# DC_Motor.net
KiCad netlist of a schematic drawn in Altium Designer
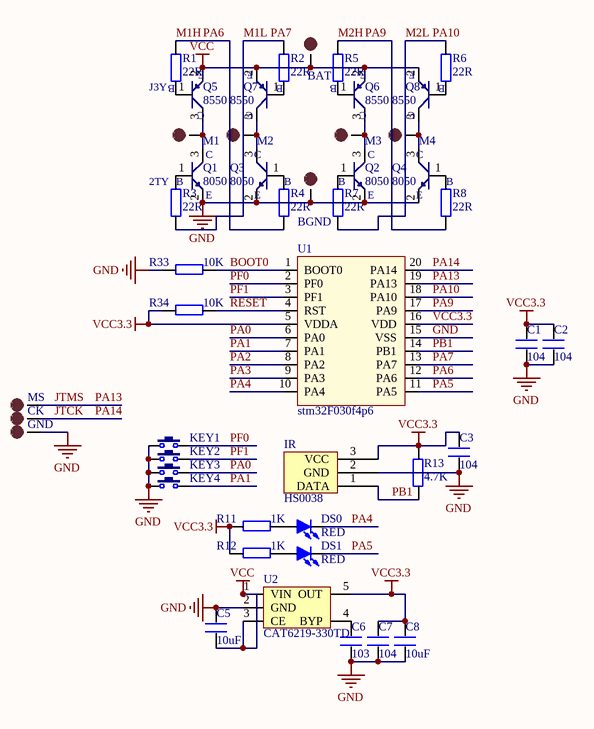
[diagram p0: DC_Motor.SchDoc]

(export (version "E")
  (design (tool "Eeschema 10.0.6"))
  (components
    (comp (ref "BAT")
      (value "TEST")
      (footprint "TP-1.5")
      (description "测试点")
      (libsource (lib "号令者I.MX RT底板封装库") (part "TEST-POINT"))
    )
    (comp (ref "BGND")
      (value "TEST")
      (footprint "TP-1.5")
      (description "测试点")
      (libsource (lib "号令者I.MX RT底板封装库") (part "TEST-POINT"))
    )
    (comp (ref "C1") (value "104") (footprint "C 0603_L") (libsource (lib "号令者I.MX RT底板封装库") (part "C")))
    (comp (ref "C2") (value "104") (footprint "C 0603_L") (libsource (lib "号令者I.MX RT底板封装库") (part "C")))
    (comp (ref "C3") (value "104") (footprint "C 0603_L") (libsource (lib "号令者I.MX RT底板封装库") (part "C")))
    (comp (ref "C5")
      (value "10uF")
      (footprint "C 0603_L")
      (libsource (lib "WarShip V3 STM32103封装库") (part "C"))
    )
    (comp (ref "C6")
      (value "103")
      (footprint "C 0603_L")
      (libsource (lib "WarShip V3 STM32103封装库") (part "C"))
    )
    (comp (ref "C7")
      (value "104")
      (footprint "C 0603_L")
      (libsource (lib "WarShip V3 STM32103封装库") (part "C"))
    )
    (comp (ref "C8")
      (value "10uF")
      (footprint "C 0603_L")
      (libsource (lib "WarShip V3 STM32103封装库") (part "C"))
    )
    (comp (ref "CK")
      (value "TEST POINT")
      (footprint "TP-1.5")
      (description "测试点")
      (libsource (lib "STM32F767核心板封装库") (part "TEST-POINT"))
    )
    (comp (ref "DS0")
      (value "RED")
      (footprint "LED 0805R")
      (description "贴片LED")
      (fields (field (name "版权归属") "源创客"))
      (libsource (lib "LED") (part "LED-SMD"))
    )
    (comp (ref "DS1")
      (value "RED")
      (footprint "LED 0805R")
      (description "贴片LED")
      (fields (field (name "版权归属") "源创客"))
      (libsource (lib "LED") (part "LED-SMD"))
    )
    (comp (ref "GND")
      (value "TEST POINT")
      (footprint "TP-1.5")
      (description "测试点")
      (libsource (lib "STM32F767核心板封装库") (part "TEST-POINT"))
    )
    (comp (ref "IR")
      (value "HS0038")
      (footprint "29-04")
      (libsource (lib "阿波罗STM32F4&F7底板封装库") (part "HS0038"))
    )
    (comp (ref "KEY1")
      (value "KEY")
      (footprint "TSW DIP-6*6*5 - 2")
      (description "按键")
      (fields (field (name "版权归属") "源创客"))
      (libsource (lib "IMX6UL_ALPHA(底板)_V2.0") (part "KEY"))
    )
    (comp (ref "KEY2")
      (value "KEY")
      (footprint "TSW DIP-6*6*5 - 2")
      (description "按键")
      (fields (field (name "版权归属") "源创客"))
      (libsource (lib "IMX6UL_ALPHA(底板)_V2.0") (part "KEY"))
    )
    (comp (ref "KEY3")
      (value "KEY")
      (footprint "TSW DIP-6*6*5 - 2")
      (description "按键")
      (fields (field (name "版权归属") "源创客"))
      (libsource (lib "IMX6UL_ALPHA(底板)_V2.0") (part "KEY"))
    )
    (comp (ref "KEY4")
      (value "KEY")
      (footprint "TSW DIP-6*6*5 - 2")
      (description "按键")
      (fields (field (name "版权归属") "源创客"))
      (libsource (lib "IMX6UL_ALPHA(底板)_V2.0") (part "KEY"))
    )
    (comp (ref "M1")
      (value "TEST")
      (footprint "TP-1.5")
      (description "测试点")
      (libsource (lib "号令者I.MX RT底板封装库") (part "TEST-POINT"))
    )
    (comp (ref "M2")
      (value "TEST")
      (footprint "TP-1.5")
      (description "测试点")
      (libsource (lib "号令者I.MX RT底板封装库") (part "TEST-POINT"))
    )
    (comp (ref "M3")
      (value "TEST")
      (footprint "TP-1.5")
      (description "测试点")
      (libsource (lib "号令者I.MX RT底板封装库") (part "TEST-POINT"))
    )
    (comp (ref "M4")
      (value "TEST")
      (footprint "TP-1.5")
      (description "测试点")
      (libsource (lib "号令者I.MX RT底板封装库") (part "TEST-POINT"))
    )
    (comp (ref "MS")
      (value "TEST POINT")
      (footprint "TP-1.5")
      (description "测试点")
      (libsource (lib "STM32F767核心板封装库") (part "TEST-POINT"))
    )
    (comp (ref "Q1") (value "8050") (footprint "SOT23-3L") (libsource (lib "ESP32_Weather") (part "8050NPN")))
    (comp (ref "Q2") (value "8050") (footprint "SOT23-3L") (libsource (lib "ESP32_Weather") (part "8050NPN")))
    (comp (ref "Q3") (value "8050") (footprint "SOT23-3L") (libsource (lib "ESP32_Weather") (part "8050NPN")))
    (comp (ref "Q4") (value "8050") (footprint "SOT23-3L") (libsource (lib "ESP32_Weather") (part "8050NPN")))
    (comp (ref "Q5") (value "8550") (footprint "SOT23-3L") (libsource (lib "ESP32_Weather") (part "8550PNP")))
    (comp (ref "Q6") (value "8550") (footprint "SOT23-3L") (libsource (lib "ESP32_Weather") (part "8550PNP")))
    (comp (ref "Q7") (value "8550") (footprint "SOT23-3L") (libsource (lib "ESP32_Weather") (part "8550PNP")))
    (comp (ref "Q8") (value "8550") (footprint "SOT23-3L") (libsource (lib "ESP32_Weather") (part "8550PNP")))
    (comp (ref "R1") (value "22R") (footprint "R 0603_L") (libsource (lib "号令者I.MX RT底板封装库") (part "R")))
    (comp (ref "R2") (value "22R") (footprint "R 0603_L") (libsource (lib "号令者I.MX RT底板封装库") (part "R")))
    (comp (ref "R3") (value "22R") (footprint "R 0603_L") (libsource (lib "号令者I.MX RT底板封装库") (part "R")))
    (comp (ref "R4") (value "22R") (footprint "R 0603_L") (libsource (lib "号令者I.MX RT底板封装库") (part "R")))
    (comp (ref "R5") (value "22R") (footprint "R 0603_L") (libsource (lib "号令者I.MX RT底板封装库") (part "R")))
    (comp (ref "R6") (value "22R") (footprint "R 0603_L") (libsource (lib "号令者I.MX RT底板封装库") (part "R")))
    (comp (ref "R7") (value "22R") (footprint "R 0603_L") (libsource (lib "号令者I.MX RT底板封装库") (part "R")))
    (comp (ref "R8") (value "22R") (footprint "R 0603_L") (libsource (lib "号令者I.MX RT底板封装库") (part "R")))
    (comp (ref "R11")
      (value "1K")
      (footprint "R 0603_L")
      (libsource (lib "WarShip V3 STM32103封装库") (part "R"))
    )
    (comp (ref "R12")
      (value "1K")
      (footprint "R 0603_L")
      (libsource (lib "WarShip V3 STM32103封装库") (part "R"))
    )
    (comp (ref "R13")
      (value "4.7K")
      (footprint "R 0603_L")
      (libsource (lib "WarShip V3 STM32103封装库") (part "R"))
    )
    (comp (ref "R33")
      (value "10K")
      (footprint "R 0603_L")
      (libsource (lib "WarShip V3 STM32103封装库") (part "R"))
    )
    (comp (ref "R34")
      (value "10K")
      (footprint "R 0603_L")
      (libsource (lib "WarShip V3 STM32103封装库") (part "R"))
    )
    (comp (ref "U1")
      (value "stm32F030f4p6")
      (footprint "TSSOP20_N")
      (libsource (lib "oled_model") (part "stm32f030"))
    )
    (comp (ref "U2")
      (value "CAT6219-330TD")
      (footprint "SOT23-5L")
      (description "3.3V 500mA LDO")
      (libsource (lib "STM32H743核心板封装库") (part "CAT6219-330TD"))
    )
  )
  (nets
    (net (code "1") (name "/BOOT0") (class "Default")
      (node (ref "R33") (pin "1") (pintype "passive"))
      (node (ref "U1") (pin "1") (pinfunction "BOOT0_1") (pintype "passive"))
    )
    (net (code "2") (name "/JTCK") (class "Default")
      (node (ref "CK") (pin "1") (pinfunction "1_1") (pintype "passive"))
      (node (ref "U1") (pin "20") (pinfunction "PA14_20") (pintype "passive"))
    )
    (net (code "3") (name "/JTMS") (class "Default")
      (node (ref "MS") (pin "1") (pinfunction "1_1") (pintype "passive"))
      (node (ref "U1") (pin "19") (pinfunction "PA13_19") (pintype "passive"))
    )
    (net (code "4") (name "/M1H") (class "Default")
      (node (ref "R1") (pin "2") (pintype "passive"))
      (node (ref "R4") (pin "1") (pintype "passive"))
      (node (ref "U1") (pin "12") (pinfunction "PA6_12") (pintype "passive"))
    )
    (net (code "5") (name "/M1L") (class "Default")
      (node (ref "R2") (pin "2") (pintype "passive"))
      (node (ref "R3") (pin "1") (pintype "passive"))
      (node (ref "U1") (pin "13") (pinfunction "PA7_13") (pintype "passive"))
    )
    (net (code "6") (name "/M2H") (class "Default")
      (node (ref "R5") (pin "2") (pintype "passive"))
      (node (ref "R8") (pin "1") (pintype "passive"))
      (node (ref "U1") (pin "17") (pinfunction "PA9_17") (pintype "passive"))
    )
    (net (code "7") (name "/M2L") (class "Default")
      (node (ref "R6") (pin "2") (pintype "passive"))
      (node (ref "R7") (pin "1") (pintype "passive"))
      (node (ref "U1") (pin "18") (pinfunction "PA10_18") (pintype "passive"))
    )
    (net (code "8") (name "/PA0") (class "Default")
      (node (ref "KEY3") (pin "2") (pinfunction "2_2") (pintype "passive"))
      (node (ref "U1") (pin "6") (pinfunction "PA0_6") (pintype "passive"))
    )
    (net (code "9") (name "/PA1") (class "Default")
      (node (ref "KEY4") (pin "2") (pinfunction "2_2") (pintype "passive"))
      (node (ref "U1") (pin "7") (pinfunction "PA1_7") (pintype "passive"))
    )
    (net (code "10") (name "/PA2") (class "Default")
      (node (ref "U1") (pin "8") (pinfunction "PA2_8") (pintype "passive"))
    )
    (net (code "11") (name "/PA3") (class "Default")
      (node (ref "U1") (pin "9") (pinfunction "PA3_9") (pintype "passive"))
    )
    (net (code "12") (name "/PA4") (class "Default")
      (node (ref "DS0") (pin "2") (pinfunction "K_2") (pintype "passive"))
      (node (ref "U1") (pin "10") (pinfunction "PA4_10") (pintype "passive"))
    )
    (net (code "13") (name "/PA5") (class "Default")
      (node (ref "DS1") (pin "2") (pinfunction "K_2") (pintype "passive"))
      (node (ref "U1") (pin "11") (pinfunction "PA5_11") (pintype "passive"))
    )
    (net (code "14") (name "/PB1") (class "Default")
      (node (ref "IR") (pin "1") (pinfunction "DATA_1") (pintype "passive"))
      (node (ref "R13") (pin "2") (pintype "passive"))
      (node (ref "U1") (pin "14") (pinfunction "PB1_14") (pintype "passive"))
    )
    (net (code "15") (name "/PF0") (class "Default")
      (node (ref "KEY1") (pin "2") (pinfunction "2_2") (pintype "passive"))
      (node (ref "U1") (pin "2") (pinfunction "PF0_2") (pintype "passive"))
    )
    (net (code "16") (name "/PF1") (class "Default")
      (node (ref "KEY2") (pin "2") (pinfunction "2_2") (pintype "passive"))
      (node (ref "U1") (pin "3") (pinfunction "PF1_3") (pintype "passive"))
    )
    (net (code "17") (name "/RESET") (class "Default")
      (node (ref "R34") (pin "1") (pintype "passive"))
      (node (ref "U1") (pin "4") (pinfunction "RST_4") (pintype "passive"))
    )
    (net (code "18") (name "GND") (class "Default")
      (node (ref "BGND") (pin "1") (pinfunction "1_1") (pintype "passive"))
      (node (ref "C1") (pin "1") (pintype "passive"))
      (node (ref "C2") (pin "1") (pintype "passive"))
      (node (ref "C3") (pin "1") (pintype "passive"))
      (node (ref "C5") (pin "2") (pintype "passive"))
      (node (ref "C6") (pin "1") (pintype "passive"))
      (node (ref "C7") (pin "1") (pintype "passive"))
      (node (ref "C8") (pin "1") (pintype "passive"))
      (node (ref "GND") (pin "1") (pinfunction "1_1") (pintype "passive"))
      (node (ref "IR") (pin "2") (pinfunction "GND_2") (pintype "passive"))
      (node (ref "KEY1") (pin "1") (pinfunction "1_1") (pintype "passive"))
      (node (ref "KEY2") (pin "1") (pinfunction "1_1") (pintype "passive"))
      (node (ref "KEY3") (pin "1") (pinfunction "1_1") (pintype "passive"))
      (node (ref "KEY4") (pin "1") (pinfunction "1_1") (pintype "passive"))
      (node (ref "Q1") (pin "2") (pinfunction "E_2") (pintype "passive"))
      (node (ref "Q2") (pin "2") (pinfunction "E_2") (pintype "passive"))
      (node (ref "Q3") (pin "2") (pinfunction "E_2") (pintype "passive"))
      (node (ref "Q4") (pin "2") (pinfunction "E_2") (pintype "passive"))
      (node (ref "R33") (pin "2") (pintype "passive"))
      (node (ref "U1") (pin "15") (pinfunction "VSS_15") (pintype "passive"))
      (node (ref "U2") (pin "2") (pinfunction "GND_2") (pintype "passive"))
    )
    (net (code "19") (name "Net-(DS0-A)") (class "Default")
      (node (ref "DS0") (pin "1") (pinfunction "A_1") (pintype "passive"))
      (node (ref "R11") (pin "1") (pintype "passive"))
    )
    (net (code "20") (name "Net-(DS1-A)") (class "Default")
      (node (ref "DS1") (pin "1") (pinfunction "A_1") (pintype "passive"))
      (node (ref "R12") (pin "1") (pintype "passive"))
    )
    (net (code "21") (name "Net-(Q1-B)") (class "Default")
      (node (ref "Q1") (pin "1") (pinfunction "B_1") (pintype "passive"))
      (node (ref "R3") (pin "2") (pintype "passive"))
    )
    (net (code "22") (name "Net-(Q1-C)") (class "Default")
      (node (ref "M1") (pin "1") (pinfunction "1_1") (pintype "passive"))
      (node (ref "Q1") (pin "3") (pinfunction "C_3") (pintype "passive"))
      (node (ref "Q5") (pin "3") (pinfunction "C_3") (pintype "passive"))
    )
    (net (code "23") (name "Net-(Q2-B)") (class "Default")
      (node (ref "Q2") (pin "1") (pinfunction "B_1") (pintype "passive"))
      (node (ref "R7") (pin "2") (pintype "passive"))
    )
    (net (code "24") (name "Net-(Q2-C)") (class "Default")
      (node (ref "M3") (pin "1") (pinfunction "1_1") (pintype "passive"))
      (node (ref "Q2") (pin "3") (pinfunction "C_3") (pintype "passive"))
      (node (ref "Q6") (pin "3") (pinfunction "C_3") (pintype "passive"))
    )
    (net (code "25") (name "Net-(Q3-B)") (class "Default")
      (node (ref "Q3") (pin "1") (pinfunction "B_1") (pintype "passive"))
      (node (ref "R4") (pin "2") (pintype "passive"))
    )
    (net (code "26") (name "Net-(Q3-C)") (class "Default")
      (node (ref "M2") (pin "1") (pinfunction "1_1") (pintype "passive"))
      (node (ref "Q3") (pin "3") (pinfunction "C_3") (pintype "passive"))
      (node (ref "Q7") (pin "3") (pinfunction "C_3") (pintype "passive"))
    )
    (net (code "27") (name "Net-(Q4-B)") (class "Default")
      (node (ref "Q4") (pin "1") (pinfunction "B_1") (pintype "passive"))
      (node (ref "R8") (pin "2") (pintype "passive"))
    )
    (net (code "28") (name "Net-(Q4-C)") (class "Default")
      (node (ref "M4") (pin "1") (pinfunction "1_1") (pintype "passive"))
      (node (ref "Q4") (pin "3") (pinfunction "C_3") (pintype "passive"))
      (node (ref "Q8") (pin "3") (pinfunction "C_3") (pintype "passive"))
    )
    (net (code "29") (name "Net-(Q5-B)") (class "Default")
      (node (ref "Q5") (pin "1") (pinfunction "B_1") (pintype "passive"))
      (node (ref "R1") (pin "1") (pintype "passive"))
    )
    (net (code "30") (name "Net-(Q6-B)") (class "Default")
      (node (ref "Q6") (pin "1") (pinfunction "B_1") (pintype "passive"))
      (node (ref "R5") (pin "1") (pintype "passive"))
    )
    (net (code "31") (name "Net-(Q7-B)") (class "Default")
      (node (ref "Q7") (pin "1") (pinfunction "B_1") (pintype "passive"))
      (node (ref "R2") (pin "1") (pintype "passive"))
    )
    (net (code "32") (name "Net-(Q8-B)") (class "Default")
      (node (ref "Q8") (pin "1") (pinfunction "B_1") (pintype "passive"))
      (node (ref "R6") (pin "1") (pintype "passive"))
    )
    (net (code "33") (name "Net-(U2-BYP)") (class "Default")
      (node (ref "C6") (pin "2") (pintype "passive"))
      (node (ref "U2") (pin "4") (pinfunction "BYP_4") (pintype "passive"))
    )
    (net (code "34") (name "VCC") (class "Default")
      (node (ref "BAT") (pin "1") (pinfunction "1_1") (pintype "passive"))
      (node (ref "C5") (pin "1") (pintype "passive"))
      (node (ref "Q5") (pin "2") (pinfunction "E_2") (pintype "passive"))
      (node (ref "Q6") (pin "2") (pinfunction "E_2") (pintype "passive"))
      (node (ref "Q7") (pin "2") (pinfunction "E_2") (pintype "passive"))
      (node (ref "Q8") (pin "2") (pinfunction "E_2") (pintype "passive"))
      (node (ref "U2") (pin "1") (pinfunction "VIN_1") (pintype "passive"))
      (node (ref "U2") (pin "3") (pinfunction "CE_3") (pintype "passive"))
    )
    (net (code "35") (name "VCC3.3") (class "Default")
      (node (ref "C1") (pin "2") (pintype "passive"))
      (node (ref "C2") (pin "2") (pintype "passive"))
      (node (ref "C3") (pin "2") (pintype "passive"))
      (node (ref "C7") (pin "2") (pintype "passive"))
      (node (ref "C8") (pin "2") (pintype "passive"))
      (node (ref "IR") (pin "3") (pinfunction "VCC_3") (pintype "passive"))
      (node (ref "R11") (pin "2") (pintype "passive"))
      (node (ref "R12") (pin "2") (pintype "passive"))
      (node (ref "R13") (pin "1") (pintype "passive"))
      (node (ref "R34") (pin "2") (pintype "passive"))
      (node (ref "U1") (pin "16") (pinfunction "VDD_16") (pintype "passive"))
      (node (ref "U1") (pin "5") (pinfunction "VDDA_5") (pintype "passive"))
      (node (ref "U2") (pin "5") (pinfunction "OUT_5") (pintype "passive"))
    )
  )
)
